# SCH_Satlla_4_Solar_unit_right_2023-01-29.net
KiCad netlist of a schematic drawn in EasyEDA
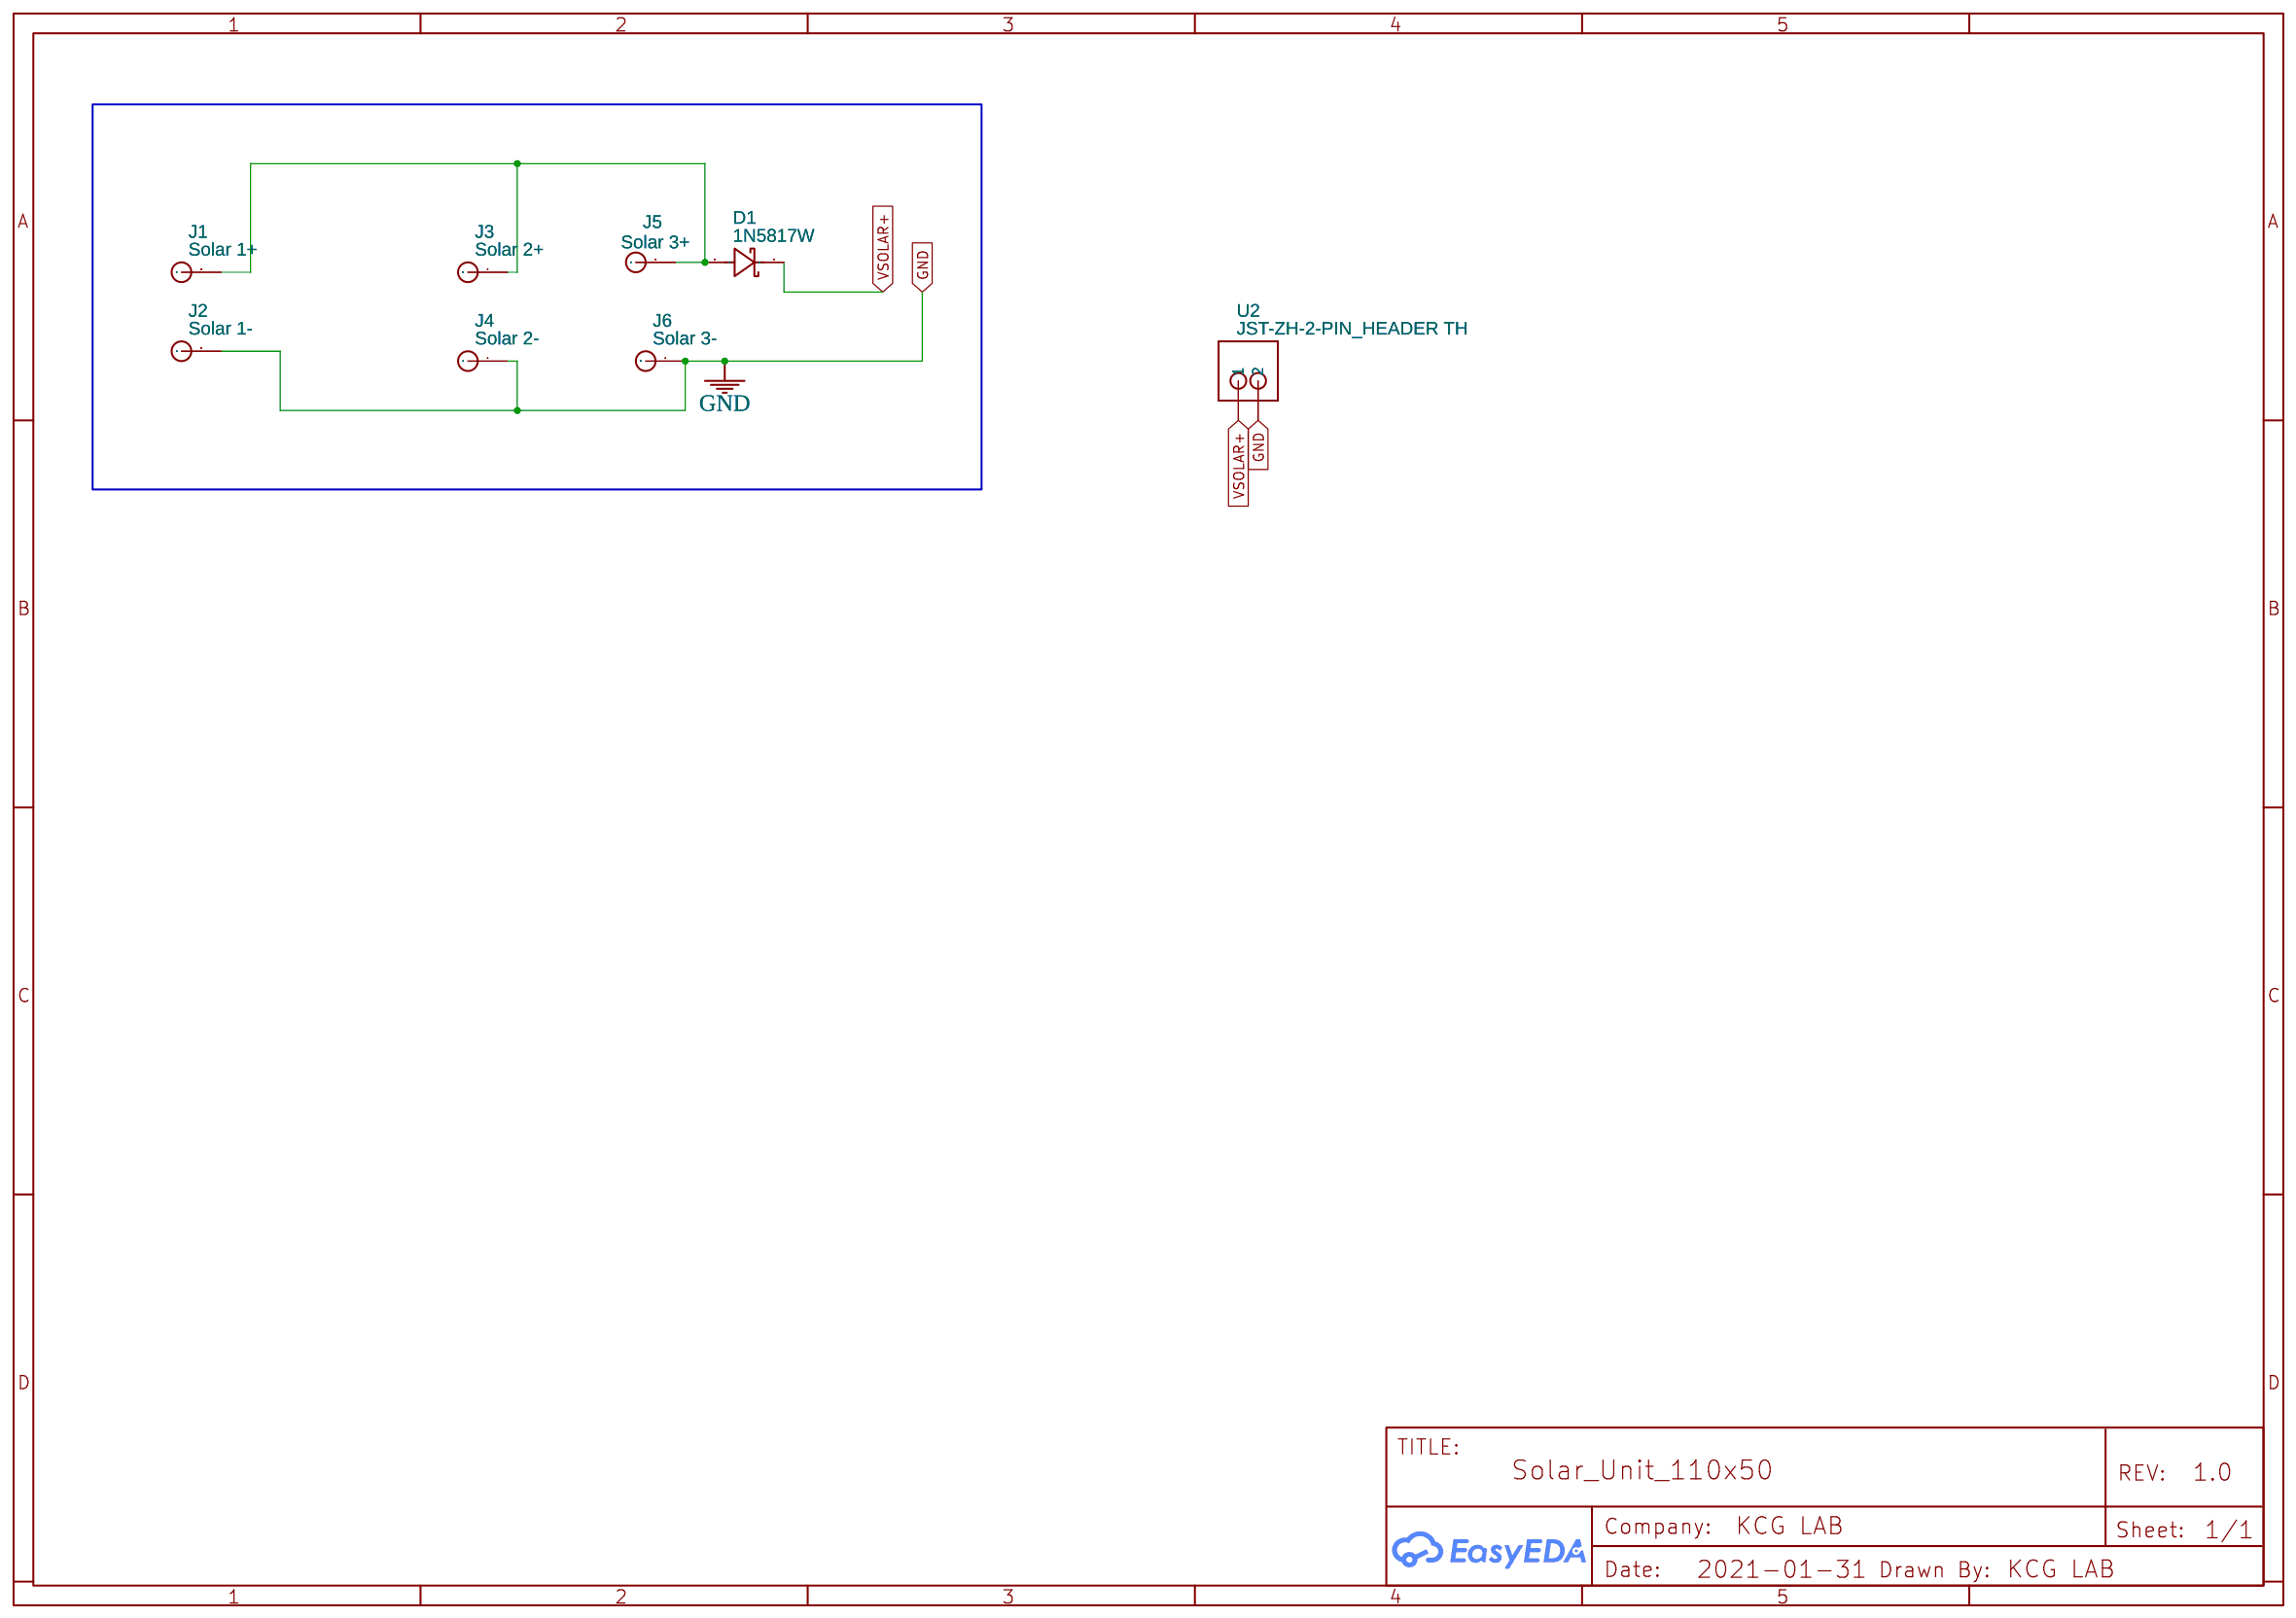
[diagram p0: schematic sheet]

(export (version "E")
  (design (tool "Eeschema 10.0.6"))
  (components
    (comp (ref "D1")
      (value "1N5817W")
      (fields (field (name "BOM_Supplier Part") "C727113"))
      (libsource (lib "") (part "1N5817W"))
    )
    (comp (ref "J1")
      (value "Solar 1+")
      (fields
        (field (name "BOM_Manufacturer Part") "RF130-1013BBS0741")
        (field (name "BOM_Supplier Part") "320030026")
      )
      (libsource (lib "") (part "Connector"))
    )
    (comp (ref "J2")
      (value "Solar 1-")
      (fields
        (field (name "BOM_Manufacturer Part") "RF130-1013BBS0741")
        (field (name "BOM_Supplier Part") "320030026")
      )
      (libsource (lib "") (part "Connector"))
    )
    (comp (ref "J3")
      (value "Solar 2+")
      (fields
        (field (name "BOM_Manufacturer Part") "RF130-1013BBS0741")
        (field (name "BOM_Supplier Part") "320030026")
      )
      (libsource (lib "") (part "Connector"))
    )
    (comp (ref "J4")
      (value "Solar 2-")
      (fields
        (field (name "BOM_Manufacturer Part") "RF130-1013BBS0741")
        (field (name "BOM_Supplier Part") "320030026")
      )
      (libsource (lib "") (part "Connector"))
    )
    (comp (ref "J5")
      (value "Solar 3+")
      (fields
        (field (name "BOM_Manufacturer Part") "RF130-1013BBS0741")
        (field (name "BOM_Supplier Part") "320030026")
      )
      (libsource (lib "") (part "Connector"))
    )
    (comp (ref "J6")
      (value "Solar 3-")
      (fields
        (field (name "BOM_Manufacturer Part") "RF130-1013BBS0741")
        (field (name "BOM_Supplier Part") "320030026")
      )
      (libsource (lib "") (part "Connector"))
    )
    (comp (ref "U2") (value "JST-ZH-2-PIN_HEADER TH") (libsource (lib "") (part "JST-ZH-2-PIN_HEADER TH")))
  )
  (nets
    (net (code "1") (name "GND") (class "Default")
      (node (ref "J2") (pin "1") (pinfunction "1_1") (pintype "unspecified"))
      (node (ref "J4") (pin "1") (pinfunction "1_1") (pintype "unspecified"))
      (node (ref "J6") (pin "1") (pinfunction "1_1") (pintype "unspecified"))
      (node (ref "U2") (pin "2") (pinfunction "2_2") (pintype "unspecified"))
    )
    (net (code "2") (name "Net-(D1-A)") (class "Default")
      (node (ref "D1") (pin "2") (pinfunction "A_2") (pintype "unspecified"))
      (node (ref "J1") (pin "1") (pinfunction "1_1") (pintype "unspecified"))
      (node (ref "J3") (pin "1") (pinfunction "1_1") (pintype "unspecified"))
      (node (ref "J5") (pin "1") (pinfunction "1_1") (pintype "unspecified"))
    )
    (net (code "3") (name "VSOLAR+") (class "Default")
      (node (ref "D1") (pin "1") (pinfunction "C_1") (pintype "unspecified"))
      (node (ref "U2") (pin "1") (pinfunction "1_1") (pintype "unspecified"))
    )
  )
)
